# EEG_1.net
KiCad netlist of a schematic drawn in Altium Designer
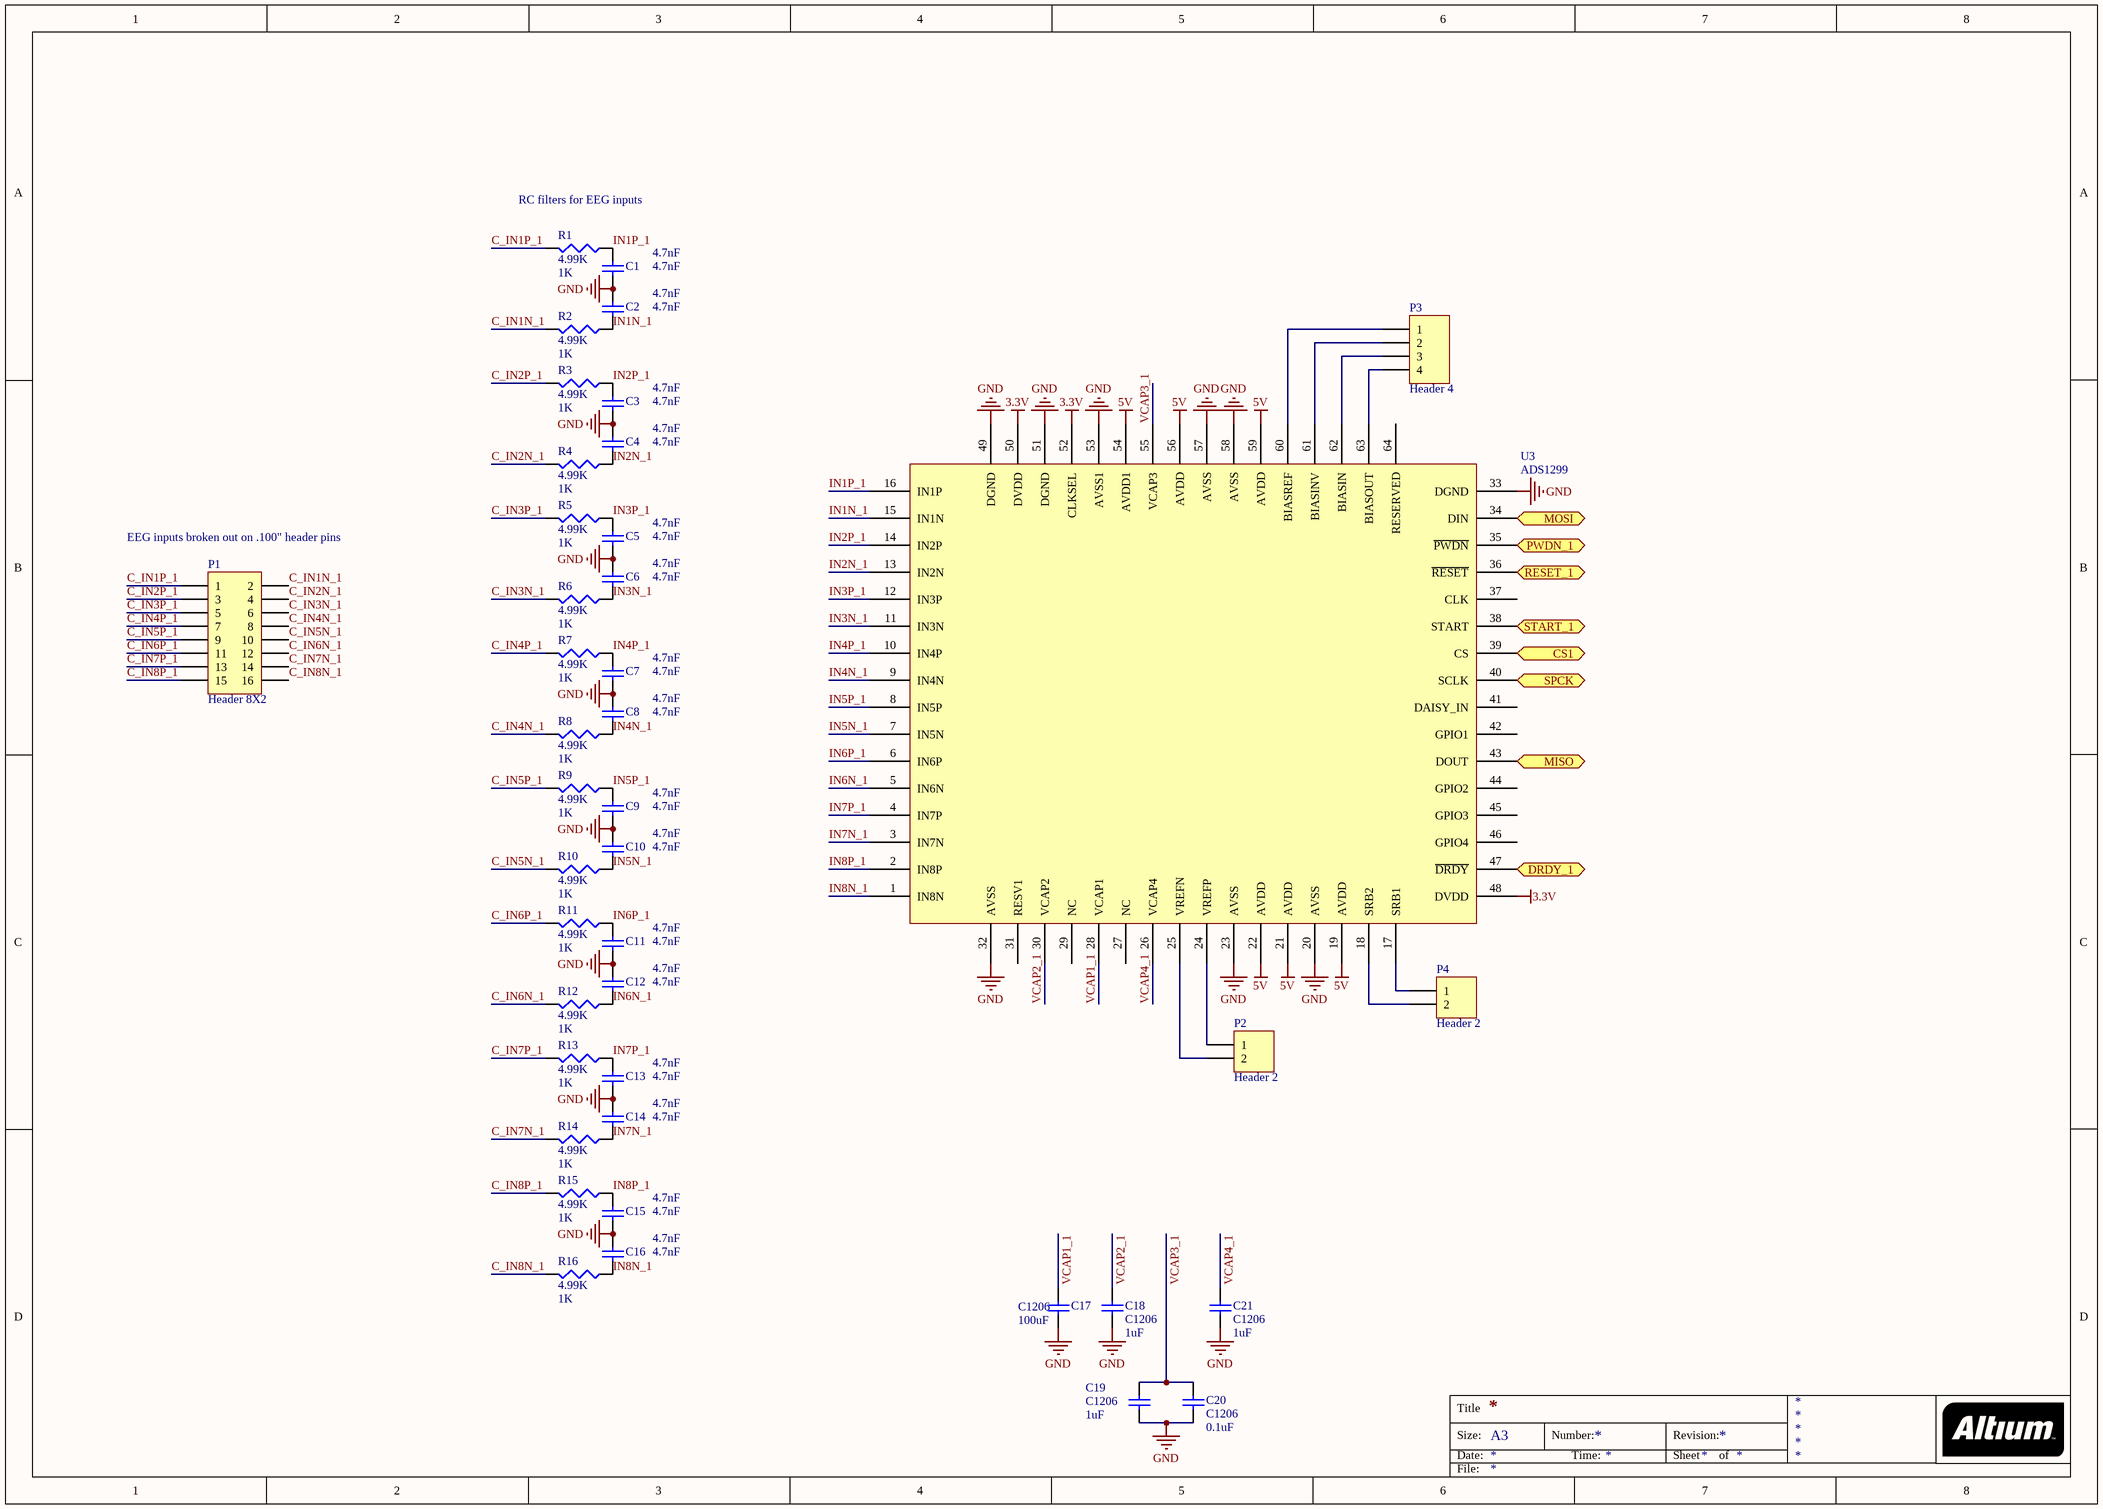
[diagram p0: EEG_1.SchDoc]

(export (version "E")
  (design (tool "Eeschema 10.0.6"))
  (components
    (comp (ref "C1")
      (value "4.7nF")
      (footprint "1608[0603]")
      (description "Capacitor (Semiconductor SIM Model)")
      (fields (field (name "ALTIUM_VALUE") "4.7nF") (field (name "PUBLISHER") "Altium Limited"))
      (libsource (lib "Miscellaneous Devices") (part "Cap Semi"))
    )
    (comp (ref "C2")
      (value "4.7nF")
      (footprint "1608[0603]")
      (description "Capacitor (Semiconductor SIM Model)")
      (fields (field (name "ALTIUM_VALUE") "4.7nF") (field (name "PUBLISHER") "Altium Limited"))
      (libsource (lib "Miscellaneous Devices") (part "Cap Semi"))
    )
    (comp (ref "C3")
      (value "4.7nF")
      (footprint "1608[0603]")
      (description "Capacitor (Semiconductor SIM Model)")
      (fields (field (name "ALTIUM_VALUE") "4.7nF") (field (name "PUBLISHER") "Altium Limited"))
      (libsource (lib "Miscellaneous Devices") (part "Cap Semi"))
    )
    (comp (ref "C4")
      (value "4.7nF")
      (footprint "1608[0603]")
      (description "Capacitor (Semiconductor SIM Model)")
      (fields (field (name "ALTIUM_VALUE") "4.7nF") (field (name "PUBLISHER") "Altium Limited"))
      (libsource (lib "Miscellaneous Devices") (part "Cap Semi"))
    )
    (comp (ref "C5")
      (value "4.7nF")
      (footprint "1608[0603]")
      (description "Capacitor (Semiconductor SIM Model)")
      (fields (field (name "ALTIUM_VALUE") "4.7nF") (field (name "PUBLISHER") "Altium Limited"))
      (libsource (lib "Miscellaneous Devices") (part "Cap Semi"))
    )
    (comp (ref "C6")
      (value "4.7nF")
      (footprint "1608[0603]")
      (description "Capacitor (Semiconductor SIM Model)")
      (fields (field (name "ALTIUM_VALUE") "4.7nF") (field (name "PUBLISHER") "Altium Limited"))
      (libsource (lib "Miscellaneous Devices") (part "Cap Semi"))
    )
    (comp (ref "C7")
      (value "4.7nF")
      (footprint "1608[0603]")
      (description "Capacitor (Semiconductor SIM Model)")
      (fields (field (name "ALTIUM_VALUE") "4.7nF") (field (name "PUBLISHER") "Altium Limited"))
      (libsource (lib "Miscellaneous Devices") (part "Cap Semi"))
    )
    (comp (ref "C8")
      (value "4.7nF")
      (footprint "1608[0603]")
      (description "Capacitor (Semiconductor SIM Model)")
      (fields (field (name "ALTIUM_VALUE") "4.7nF") (field (name "PUBLISHER") "Altium Limited"))
      (libsource (lib "Miscellaneous Devices") (part "Cap Semi"))
    )
    (comp (ref "C9")
      (value "4.7nF")
      (footprint "1608[0603]")
      (description "Capacitor (Semiconductor SIM Model)")
      (fields (field (name "ALTIUM_VALUE") "4.7nF") (field (name "PUBLISHER") "Altium Limited"))
      (libsource (lib "Miscellaneous Devices") (part "Cap Semi"))
    )
    (comp (ref "C10")
      (value "4.7nF")
      (footprint "1608[0603]")
      (description "Capacitor (Semiconductor SIM Model)")
      (fields (field (name "ALTIUM_VALUE") "4.7nF") (field (name "PUBLISHER") "Altium Limited"))
      (libsource (lib "Miscellaneous Devices") (part "Cap Semi"))
    )
    (comp (ref "C11")
      (value "4.7nF")
      (footprint "1608[0603]")
      (description "Capacitor (Semiconductor SIM Model)")
      (fields (field (name "ALTIUM_VALUE") "4.7nF") (field (name "PUBLISHER") "Altium Limited"))
      (libsource (lib "Miscellaneous Devices") (part "Cap Semi"))
    )
    (comp (ref "C12")
      (value "4.7nF")
      (footprint "1608[0603]")
      (description "Capacitor (Semiconductor SIM Model)")
      (fields (field (name "ALTIUM_VALUE") "4.7nF") (field (name "PUBLISHER") "Altium Limited"))
      (libsource (lib "Miscellaneous Devices") (part "Cap Semi"))
    )
    (comp (ref "C13")
      (value "4.7nF")
      (footprint "1608[0603]")
      (description "Capacitor (Semiconductor SIM Model)")
      (fields (field (name "ALTIUM_VALUE") "4.7nF") (field (name "PUBLISHER") "Altium Limited"))
      (libsource (lib "Miscellaneous Devices") (part "Cap Semi"))
    )
    (comp (ref "C14")
      (value "4.7nF")
      (footprint "1608[0603]")
      (description "Capacitor (Semiconductor SIM Model)")
      (fields (field (name "ALTIUM_VALUE") "4.7nF") (field (name "PUBLISHER") "Altium Limited"))
      (libsource (lib "Miscellaneous Devices") (part "Cap Semi"))
    )
    (comp (ref "C15")
      (value "4.7nF")
      (footprint "1608[0603]")
      (description "Capacitor (Semiconductor SIM Model)")
      (fields (field (name "ALTIUM_VALUE") "4.7nF") (field (name "PUBLISHER") "Altium Limited"))
      (libsource (lib "Miscellaneous Devices") (part "Cap Semi"))
    )
    (comp (ref "C16")
      (value "4.7nF")
      (footprint "1608[0603]")
      (description "Capacitor (Semiconductor SIM Model)")
      (fields (field (name "ALTIUM_VALUE") "4.7nF") (field (name "PUBLISHER") "Altium Limited"))
      (libsource (lib "Miscellaneous Devices") (part "Cap Semi"))
    )
    (comp (ref "C17")
      (value "C1206")
      (footprint "1608[0603]")
      (description "Capacitor (Semiconductor SIM Model)")
      (fields (field (name "ALTIUM_VALUE") "100uF") (field (name "PUBLISHER") "Altium Limited"))
      (libsource (lib "Miscellaneous Devices") (part "Cap Semi"))
    )
    (comp (ref "C18")
      (value "C1206")
      (footprint "1608[0603]")
      (description "Capacitor (Semiconductor SIM Model)")
      (fields (field (name "ALTIUM_VALUE") "1uF") (field (name "PUBLISHER") "Altium Limited"))
      (libsource (lib "Miscellaneous Devices") (part "Cap Semi"))
    )
    (comp (ref "C19")
      (value "C1206")
      (footprint "1608[0603]")
      (description "Capacitor (Semiconductor SIM Model)")
      (fields (field (name "ALTIUM_VALUE") "1uF") (field (name "PUBLISHER") "Altium Limited"))
      (libsource (lib "Miscellaneous Devices") (part "Cap Semi"))
    )
    (comp (ref "C20")
      (value "C1206")
      (footprint "1608[0603]")
      (description "Capacitor (Semiconductor SIM Model)")
      (fields (field (name "ALTIUM_VALUE") "0.1uF") (field (name "PUBLISHER") "Altium Limited"))
      (libsource (lib "Miscellaneous Devices") (part "Cap Semi"))
    )
    (comp (ref "C21")
      (value "C1206")
      (footprint "1608[0603]")
      (description "Capacitor (Semiconductor SIM Model)")
      (fields (field (name "ALTIUM_VALUE") "1uF") (field (name "PUBLISHER") "Altium Limited"))
      (libsource (lib "Miscellaneous Devices") (part "Cap Semi"))
    )
    (comp (ref "P1")
      (value "Header 8X2")
      (footprint "HDR2X8")
      (description "Header, 8-Pin, Dual row")
      (fields (field (name "PUBLISHER") "Altium Limited"))
      (libsource (lib "Miscellaneous Connectors") (part "Header 8X2"))
    )
    (comp (ref "P2")
      (value "Header 2")
      (footprint "HDR1X2")
      (description "Header, 2-Pin")
      (fields (field (name "PUBLISHER") "Altium Limited"))
      (libsource (lib "Miscellaneous Connectors") (part "Header 2"))
    )
    (comp (ref "P3")
      (value "Header 4")
      (footprint "HDR1X4")
      (description "Header, 4-Pin")
      (fields (field (name "PUBLISHER") "Altium Limited"))
      (libsource (lib "Miscellaneous Connectors") (part "Header 4"))
    )
    (comp (ref "P4")
      (value "Header 2")
      (footprint "HDR1X2")
      (description "Header, 2-Pin")
      (fields (field (name "PUBLISHER") "Altium Limited"))
      (libsource (lib "Miscellaneous Connectors") (part "Header 2"))
    )
    (comp (ref "R1")
      (value "4.99K")
      (footprint "1608[0603]")
      (description "Resistor")
      (fields (field (name "ALTIUM_VALUE") "1K") (field (name "PUBLISHER") "Altium Limited"))
      (libsource (lib "Miscellaneous Devices") (part "Res3"))
    )
    (comp (ref "R2")
      (value "4.99K")
      (footprint "1608[0603]")
      (description "Resistor")
      (fields (field (name "ALTIUM_VALUE") "1K") (field (name "PUBLISHER") "Altium Limited"))
      (libsource (lib "Miscellaneous Devices") (part "Res3"))
    )
    (comp (ref "R3")
      (value "4.99K")
      (footprint "1608[0603]")
      (description "Resistor")
      (fields (field (name "ALTIUM_VALUE") "1K") (field (name "PUBLISHER") "Altium Limited"))
      (libsource (lib "Miscellaneous Devices") (part "Res3"))
    )
    (comp (ref "R4")
      (value "4.99K")
      (footprint "1608[0603]")
      (description "Resistor")
      (fields (field (name "ALTIUM_VALUE") "1K") (field (name "PUBLISHER") "Altium Limited"))
      (libsource (lib "Miscellaneous Devices") (part "Res3"))
    )
    (comp (ref "R5")
      (value "4.99K")
      (footprint "1608[0603]")
      (description "Resistor")
      (fields (field (name "ALTIUM_VALUE") "1K") (field (name "PUBLISHER") "Altium Limited"))
      (libsource (lib "Miscellaneous Devices") (part "Res3"))
    )
    (comp (ref "R6")
      (value "4.99K")
      (footprint "1608[0603]")
      (description "Resistor")
      (fields (field (name "ALTIUM_VALUE") "1K") (field (name "PUBLISHER") "Altium Limited"))
      (libsource (lib "Miscellaneous Devices") (part "Res3"))
    )
    (comp (ref "R7")
      (value "4.99K")
      (footprint "1608[0603]")
      (description "Resistor")
      (fields (field (name "ALTIUM_VALUE") "1K") (field (name "PUBLISHER") "Altium Limited"))
      (libsource (lib "Miscellaneous Devices") (part "Res3"))
    )
    (comp (ref "R8")
      (value "4.99K")
      (footprint "1608[0603]")
      (description "Resistor")
      (fields (field (name "ALTIUM_VALUE") "1K") (field (name "PUBLISHER") "Altium Limited"))
      (libsource (lib "Miscellaneous Devices") (part "Res3"))
    )
    (comp (ref "R9")
      (value "4.99K")
      (footprint "1608[0603]")
      (description "Resistor")
      (fields (field (name "ALTIUM_VALUE") "1K") (field (name "PUBLISHER") "Altium Limited"))
      (libsource (lib "Miscellaneous Devices") (part "Res3"))
    )
    (comp (ref "R10")
      (value "4.99K")
      (footprint "1608[0603]")
      (description "Resistor")
      (fields (field (name "ALTIUM_VALUE") "1K") (field (name "PUBLISHER") "Altium Limited"))
      (libsource (lib "Miscellaneous Devices") (part "Res3"))
    )
    (comp (ref "R11")
      (value "4.99K")
      (footprint "1608[0603]")
      (description "Resistor")
      (fields (field (name "ALTIUM_VALUE") "1K") (field (name "PUBLISHER") "Altium Limited"))
      (libsource (lib "Miscellaneous Devices") (part "Res3"))
    )
    (comp (ref "R12")
      (value "4.99K")
      (footprint "1608[0603]")
      (description "Resistor")
      (fields (field (name "ALTIUM_VALUE") "1K") (field (name "PUBLISHER") "Altium Limited"))
      (libsource (lib "Miscellaneous Devices") (part "Res3"))
    )
    (comp (ref "R13")
      (value "4.99K")
      (footprint "1608[0603]")
      (description "Resistor")
      (fields (field (name "ALTIUM_VALUE") "1K") (field (name "PUBLISHER") "Altium Limited"))
      (libsource (lib "Miscellaneous Devices") (part "Res3"))
    )
    (comp (ref "R14")
      (value "4.99K")
      (footprint "1608[0603]")
      (description "Resistor")
      (fields (field (name "ALTIUM_VALUE") "1K") (field (name "PUBLISHER") "Altium Limited"))
      (libsource (lib "Miscellaneous Devices") (part "Res3"))
    )
    (comp (ref "R15")
      (value "4.99K")
      (footprint "1608[0603]")
      (description "Resistor")
      (fields (field (name "ALTIUM_VALUE") "1K") (field (name "PUBLISHER") "Altium Limited"))
      (libsource (lib "Miscellaneous Devices") (part "Res3"))
    )
    (comp (ref "R16")
      (value "4.99K")
      (footprint "1608[0603]")
      (description "Resistor")
      (fields (field (name "ALTIUM_VALUE") "1K") (field (name "PUBLISHER") "Altium Limited"))
      (libsource (lib "Miscellaneous Devices") (part "Res3"))
    )
    (comp (ref "U3")
      (value "ADS1299")
      (footprint "ADS1299 Plastic QFP")
      (libsource (lib "ADS1299") (part "ADS1299"))
    )
  )
  (nets
    (net (code "1") (name "/CS1") (class "Default")
      (node (ref "U3") (pin "39") (pinfunction "CS_39") (pintype "passive"))
    )
    (net (code "2") (name "/C_IN1N_1") (class "Default")
      (node (ref "P1") (pin "2") (pinfunction "2_2") (pintype "passive"))
      (node (ref "R2") (pin "2") (pinfunction "2_2") (pintype "passive"))
    )
    (net (code "3") (name "/C_IN1P_1") (class "Default")
      (node (ref "P1") (pin "1") (pinfunction "1_1") (pintype "passive"))
      (node (ref "R1") (pin "2") (pinfunction "2_2") (pintype "passive"))
    )
    (net (code "4") (name "/C_IN2N_1") (class "Default")
      (node (ref "P1") (pin "4") (pinfunction "4_4") (pintype "passive"))
      (node (ref "R4") (pin "2") (pinfunction "2_2") (pintype "passive"))
    )
    (net (code "5") (name "/C_IN2P_1") (class "Default")
      (node (ref "P1") (pin "3") (pinfunction "3_3") (pintype "passive"))
      (node (ref "R3") (pin "2") (pinfunction "2_2") (pintype "passive"))
    )
    (net (code "6") (name "/C_IN3N_1") (class "Default")
      (node (ref "P1") (pin "6") (pinfunction "6_6") (pintype "passive"))
      (node (ref "R6") (pin "2") (pinfunction "2_2") (pintype "passive"))
    )
    (net (code "7") (name "/C_IN3P_1") (class "Default")
      (node (ref "P1") (pin "5") (pinfunction "5_5") (pintype "passive"))
      (node (ref "R5") (pin "2") (pinfunction "2_2") (pintype "passive"))
    )
    (net (code "8") (name "/C_IN4N_1") (class "Default")
      (node (ref "P1") (pin "8") (pinfunction "8_8") (pintype "passive"))
      (node (ref "R8") (pin "2") (pinfunction "2_2") (pintype "passive"))
    )
    (net (code "9") (name "/C_IN4P_1") (class "Default")
      (node (ref "P1") (pin "7") (pinfunction "7_7") (pintype "passive"))
      (node (ref "R7") (pin "2") (pinfunction "2_2") (pintype "passive"))
    )
    (net (code "10") (name "/C_IN5N_1") (class "Default")
      (node (ref "P1") (pin "10") (pinfunction "10_10") (pintype "passive"))
      (node (ref "R10") (pin "2") (pinfunction "2_2") (pintype "passive"))
    )
    (net (code "11") (name "/C_IN5P_1") (class "Default")
      (node (ref "P1") (pin "9") (pinfunction "9_9") (pintype "passive"))
      (node (ref "R9") (pin "2") (pinfunction "2_2") (pintype "passive"))
    )
    (net (code "12") (name "/C_IN6N_1") (class "Default")
      (node (ref "P1") (pin "12") (pinfunction "12_12") (pintype "passive"))
      (node (ref "R12") (pin "2") (pinfunction "2_2") (pintype "passive"))
    )
    (net (code "13") (name "/C_IN6P_1") (class "Default")
      (node (ref "P1") (pin "11") (pinfunction "11_11") (pintype "passive"))
      (node (ref "R11") (pin "2") (pinfunction "2_2") (pintype "passive"))
    )
    (net (code "14") (name "/C_IN7N_1") (class "Default")
      (node (ref "P1") (pin "14") (pinfunction "14_14") (pintype "passive"))
      (node (ref "R14") (pin "2") (pinfunction "2_2") (pintype "passive"))
    )
    (net (code "15") (name "/C_IN7P_1") (class "Default")
      (node (ref "P1") (pin "13") (pinfunction "13_13") (pintype "passive"))
      (node (ref "R13") (pin "2") (pinfunction "2_2") (pintype "passive"))
    )
    (net (code "16") (name "/C_IN8N_1") (class "Default")
      (node (ref "P1") (pin "16") (pinfunction "16_16") (pintype "passive"))
      (node (ref "R16") (pin "2") (pinfunction "2_2") (pintype "passive"))
    )
    (net (code "17") (name "/C_IN8P_1") (class "Default")
      (node (ref "P1") (pin "15") (pinfunction "15_15") (pintype "passive"))
      (node (ref "R15") (pin "2") (pinfunction "2_2") (pintype "passive"))
    )
    (net (code "18") (name "/DRDY_1") (class "Default")
      (node (ref "U3") (pin "47") (pinfunction "~{DRDY}_47") (pintype "passive"))
    )
    (net (code "19") (name "/IN1N_1") (class "Default")
      (node (ref "C2") (pin "1") (pinfunction "1_1") (pintype "passive"))
      (node (ref "R2") (pin "1") (pinfunction "1_1") (pintype "passive"))
      (node (ref "U3") (pin "15") (pinfunction "IN1N_15") (pintype "passive"))
    )
    (net (code "20") (name "/IN1P_1") (class "Default")
      (node (ref "C1") (pin "2") (pinfunction "2_2") (pintype "passive"))
      (node (ref "R1") (pin "1") (pinfunction "1_1") (pintype "passive"))
      (node (ref "U3") (pin "16") (pinfunction "IN1P_16") (pintype "passive"))
    )
    (net (code "21") (name "/IN2N_1") (class "Default")
      (node (ref "C4") (pin "1") (pinfunction "1_1") (pintype "passive"))
      (node (ref "R4") (pin "1") (pinfunction "1_1") (pintype "passive"))
      (node (ref "U3") (pin "13") (pinfunction "IN2N_13") (pintype "passive"))
    )
    (net (code "22") (name "/IN2P_1") (class "Default")
      (node (ref "C3") (pin "2") (pinfunction "2_2") (pintype "passive"))
      (node (ref "R3") (pin "1") (pinfunction "1_1") (pintype "passive"))
      (node (ref "U3") (pin "14") (pinfunction "IN2P_14") (pintype "passive"))
    )
    (net (code "23") (name "/IN3N_1") (class "Default")
      (node (ref "C6") (pin "1") (pinfunction "1_1") (pintype "passive"))
      (node (ref "R6") (pin "1") (pinfunction "1_1") (pintype "passive"))
      (node (ref "U3") (pin "11") (pinfunction "IN3N_11") (pintype "passive"))
    )
    (net (code "24") (name "/IN3P_1") (class "Default")
      (node (ref "C5") (pin "2") (pinfunction "2_2") (pintype "passive"))
      (node (ref "R5") (pin "1") (pinfunction "1_1") (pintype "passive"))
      (node (ref "U3") (pin "12") (pinfunction "IN3P_12") (pintype "passive"))
    )
    (net (code "25") (name "/IN4N_1") (class "Default")
      (node (ref "C8") (pin "1") (pinfunction "1_1") (pintype "passive"))
      (node (ref "R8") (pin "1") (pinfunction "1_1") (pintype "passive"))
      (node (ref "U3") (pin "9") (pinfunction "IN4N_9") (pintype "passive"))
    )
    (net (code "26") (name "/IN4P_1") (class "Default")
      (node (ref "C7") (pin "2") (pinfunction "2_2") (pintype "passive"))
      (node (ref "R7") (pin "1") (pinfunction "1_1") (pintype "passive"))
      (node (ref "U3") (pin "10") (pinfunction "IN4P_10") (pintype "passive"))
    )
    (net (code "27") (name "/IN5N_1") (class "Default")
      (node (ref "C10") (pin "1") (pinfunction "1_1") (pintype "passive"))
      (node (ref "R10") (pin "1") (pinfunction "1_1") (pintype "passive"))
      (node (ref "U3") (pin "7") (pinfunction "IN5N_7") (pintype "passive"))
    )
    (net (code "28") (name "/IN5P_1") (class "Default")
      (node (ref "C9") (pin "2") (pinfunction "2_2") (pintype "passive"))
      (node (ref "R9") (pin "1") (pinfunction "1_1") (pintype "passive"))
      (node (ref "U3") (pin "8") (pinfunction "IN5P_8") (pintype "passive"))
    )
    (net (code "29") (name "/IN6N_1") (class "Default")
      (node (ref "C12") (pin "1") (pinfunction "1_1") (pintype "passive"))
      (node (ref "R12") (pin "1") (pinfunction "1_1") (pintype "passive"))
      (node (ref "U3") (pin "5") (pinfunction "IN6N_5") (pintype "passive"))
    )
    (net (code "30") (name "/IN6P_1") (class "Default")
      (node (ref "C11") (pin "2") (pinfunction "2_2") (pintype "passive"))
      (node (ref "R11") (pin "1") (pinfunction "1_1") (pintype "passive"))
      (node (ref "U3") (pin "6") (pinfunction "IN6P_6") (pintype "passive"))
    )
    (net (code "31") (name "/IN7N_1") (class "Default")
      (node (ref "C14") (pin "1") (pinfunction "1_1") (pintype "passive"))
      (node (ref "R14") (pin "1") (pinfunction "1_1") (pintype "passive"))
      (node (ref "U3") (pin "3") (pinfunction "IN7N_3") (pintype "passive"))
    )
    (net (code "32") (name "/IN7P_1") (class "Default")
      (node (ref "C13") (pin "2") (pinfunction "2_2") (pintype "passive"))
      (node (ref "R13") (pin "1") (pinfunction "1_1") (pintype "passive"))
      (node (ref "U3") (pin "4") (pinfunction "IN7P_4") (pintype "passive"))
    )
    (net (code "33") (name "/IN8N_1") (class "Default")
      (node (ref "C16") (pin "1") (pinfunction "1_1") (pintype "passive"))
      (node (ref "R16") (pin "1") (pinfunction "1_1") (pintype "passive"))
      (node (ref "U3") (pin "1") (pinfunction "IN8N_1") (pintype "passive"))
    )
    (net (code "34") (name "/IN8P_1") (class "Default")
      (node (ref "C15") (pin "2") (pinfunction "2_2") (pintype "passive"))
      (node (ref "R15") (pin "1") (pinfunction "1_1") (pintype "passive"))
      (node (ref "U3") (pin "2") (pinfunction "IN8P_2") (pintype "passive"))
    )
    (net (code "35") (name "/MISO") (class "Default")
      (node (ref "U3") (pin "43") (pinfunction "DOUT_43") (pintype "passive"))
    )
    (net (code "36") (name "/MOSI") (class "Default")
      (node (ref "U3") (pin "34") (pinfunction "DIN_34") (pintype "passive"))
    )
    (net (code "37") (name "/PWDN_1") (class "Default")
      (node (ref "U3") (pin "35") (pinfunction "~{PWDN}_35") (pintype "passive"))
    )
    (net (code "38") (name "/RESET_1") (class "Default")
      (node (ref "U3") (pin "36") (pinfunction "~{RESET}_36") (pintype "passive"))
    )
    (net (code "39") (name "/SPCK") (class "Default")
      (node (ref "U3") (pin "40") (pinfunction "SCLK_40") (pintype "passive"))
    )
    (net (code "40") (name "/START_1") (class "Default")
      (node (ref "U3") (pin "38") (pinfunction "START_38") (pintype "passive"))
    )
    (net (code "41") (name "/VCAP1_1") (class "Default")
      (node (ref "C17") (pin "1") (pinfunction "1_1") (pintype "passive"))
      (node (ref "U3") (pin "28") (pinfunction "VCAP1_28") (pintype "passive"))
    )
    (net (code "42") (name "/VCAP2_1") (class "Default")
      (node (ref "C18") (pin "2") (pinfunction "2_2") (pintype "passive"))
      (node (ref "U3") (pin "30") (pinfunction "VCAP2_30") (pintype "passive"))
    )
    (net (code "43") (name "/VCAP3_1") (class "Default")
      (node (ref "C19") (pin "1") (pinfunction "1_1") (pintype "passive"))
      (node (ref "C20") (pin "2") (pinfunction "2_2") (pintype "passive"))
      (node (ref "U3") (pin "55") (pinfunction "VCAP3_55") (pintype "passive"))
    )
    (net (code "44") (name "/VCAP4_1") (class "Default")
      (node (ref "C21") (pin "2") (pinfunction "2_2") (pintype "passive"))
      (node (ref "U3") (pin "26") (pinfunction "VCAP4_26") (pintype "passive"))
    )
    (net (code "45") (name "3.3V") (class "Default")
      (node (ref "U3") (pin "48") (pinfunction "DVDD_48") (pintype "passive"))
      (node (ref "U3") (pin "50") (pinfunction "DVDD_50") (pintype "passive"))
      (node (ref "U3") (pin "52") (pinfunction "CLKSEL_52") (pintype "passive"))
    )
    (net (code "46") (name "5V") (class "Default")
      (node (ref "U3") (pin "19") (pinfunction "AVDD_19") (pintype "passive"))
      (node (ref "U3") (pin "21") (pinfunction "AVDD_21") (pintype "passive"))
      (node (ref "U3") (pin "22") (pinfunction "AVDD_22") (pintype "passive"))
      (node (ref "U3") (pin "54") (pinfunction "AVDD1_54") (pintype "passive"))
      (node (ref "U3") (pin "56") (pinfunction "AVDD_56") (pintype "passive"))
      (node (ref "U3") (pin "59") (pinfunction "AVDD_59") (pintype "passive"))
    )
    (net (code "47") (name "GND") (class "Default")
      (node (ref "C1") (pin "1") (pinfunction "1_1") (pintype "passive"))
      (node (ref "C10") (pin "2") (pinfunction "2_2") (pintype "passive"))
      (node (ref "C11") (pin "1") (pinfunction "1_1") (pintype "passive"))
      (node (ref "C12") (pin "2") (pinfunction "2_2") (pintype "passive"))
      (node (ref "C13") (pin "1") (pinfunction "1_1") (pintype "passive"))
      (node (ref "C14") (pin "2") (pinfunction "2_2") (pintype "passive"))
      (node (ref "C15") (pin "1") (pinfunction "1_1") (pintype "passive"))
      (node (ref "C16") (pin "2") (pinfunction "2_2") (pintype "passive"))
      (node (ref "C17") (pin "2") (pinfunction "2_2") (pintype "passive"))
      (node (ref "C18") (pin "1") (pinfunction "1_1") (pintype "passive"))
      (node (ref "C19") (pin "2") (pinfunction "2_2") (pintype "passive"))
      (node (ref "C2") (pin "2") (pinfunction "2_2") (pintype "passive"))
      (node (ref "C20") (pin "1") (pinfunction "1_1") (pintype "passive"))
      (node (ref "C21") (pin "1") (pinfunction "1_1") (pintype "passive"))
      (node (ref "C3") (pin "1") (pinfunction "1_1") (pintype "passive"))
      (node (ref "C4") (pin "2") (pinfunction "2_2") (pintype "passive"))
      (node (ref "C5") (pin "1") (pinfunction "1_1") (pintype "passive"))
      (node (ref "C6") (pin "2") (pinfunction "2_2") (pintype "passive"))
      (node (ref "C7") (pin "1") (pinfunction "1_1") (pintype "passive"))
      (node (ref "C8") (pin "2") (pinfunction "2_2") (pintype "passive"))
      (node (ref "C9") (pin "1") (pinfunction "1_1") (pintype "passive"))
      (node (ref "U3") (pin "20") (pinfunction "AVSS_20") (pintype "passive"))
      (node (ref "U3") (pin "23") (pinfunction "AVSS_23") (pintype "passive"))
      (node (ref "U3") (pin "32") (pinfunction "AVSS_32") (pintype "passive"))
      (node (ref "U3") (pin "33") (pinfunction "DGND_33") (pintype "passive"))
      (node (ref "U3") (pin "49") (pinfunction "DGND_49") (pintype "passive"))
      (node (ref "U3") (pin "51") (pinfunction "DGND_51") (pintype "passive"))
      (node (ref "U3") (pin "53") (pinfunction "AVSS1_53") (pintype "passive"))
      (node (ref "U3") (pin "57") (pinfunction "AVSS_57") (pintype "passive"))
      (node (ref "U3") (pin "58") (pinfunction "AVSS_58") (pintype "passive"))
    )
    (net (code "48") (name "Net-(U3-BIASIN)") (class "Default")
      (node (ref "P3") (pin "3") (pinfunction "3_3") (pintype "passive"))
      (node (ref "U3") (pin "62") (pinfunction "BIASIN_62") (pintype "passive"))
    )
    (net (code "49") (name "Net-(U3-BIASINV)") (class "Default")
      (node (ref "P3") (pin "2") (pinfunction "2_2") (pintype "passive"))
      (node (ref "U3") (pin "61") (pinfunction "BIASINV_61") (pintype "passive"))
    )
    (net (code "50") (name "Net-(U3-BIASOUT)") (class "Default")
      (node (ref "P3") (pin "4") (pinfunction "4_4") (pintype "passive"))
      (node (ref "U3") (pin "63") (pinfunction "BIASOUT_63") (pintype "passive"))
    )
    (net (code "51") (name "Net-(U3-BIASREF)") (class "Default")
      (node (ref "P3") (pin "1") (pinfunction "1_1") (pintype "passive"))
      (node (ref "U3") (pin "60") (pinfunction "BIASREF_60") (pintype "passive"))
    )
    (net (code "52") (name "Net-(U3-SRB1)") (class "Default")
      (node (ref "P4") (pin "1") (pinfunction "1_1") (pintype "passive"))
      (node (ref "U3") (pin "17") (pinfunction "SRB1_17") (pintype "passive"))
    )
    (net (code "53") (name "Net-(U3-SRB2)") (class "Default")
      (node (ref "P4") (pin "2") (pinfunction "2_2") (pintype "passive"))
      (node (ref "U3") (pin "18") (pinfunction "SRB2_18") (pintype "passive"))
    )
    (net (code "54") (name "Net-(U3-VREFN)") (class "Default")
      (node (ref "P2") (pin "2") (pinfunction "2_2") (pintype "passive"))
      (node (ref "U3") (pin "25") (pinfunction "VREFN_25") (pintype "passive"))
    )
    (net (code "55") (name "Net-(U3-VREFP)") (class "Default")
      (node (ref "P2") (pin "1") (pinfunction "1_1") (pintype "passive"))
      (node (ref "U3") (pin "24") (pinfunction "VREFP_24") (pintype "passive"))
    )
    (net (code "56") (name "unconnected-(U3-CLK-Pad37)") (class "Default")
      (node (ref "U3") (pin "37") (pinfunction "CLK_37") (pintype "passive"))
    )
    (net (code "57") (name "unconnected-(U3-DAISY_IN-Pad41)") (class "Default")
      (node (ref "U3") (pin "41") (pinfunction "DAISY_IN_41") (pintype "passive"))
    )
    (net (code "58") (name "unconnected-(U3-GPIO1-Pad42)") (class "Default")
      (node (ref "U3") (pin "42") (pinfunction "GPIO1_42") (pintype "passive"))
    )
    (net (code "59") (name "unconnected-(U3-GPIO2-Pad44)") (class "Default")
      (node (ref "U3") (pin "44") (pinfunction "GPIO2_44") (pintype "passive"))
    )
    (net (code "60") (name "unconnected-(U3-GPIO3-Pad45)") (class "Default")
      (node (ref "U3") (pin "45") (pinfunction "GPIO3_45") (pintype "passive"))
    )
    (net (code "61") (name "unconnected-(U3-GPIO4-Pad46)") (class "Default")
      (node (ref "U3") (pin "46") (pinfunction "GPIO4_46") (pintype "passive"))
    )
    (net (code "62") (name "unconnected-(U3-NC-Pad27)") (class "Default")
      (node (ref "U3") (pin "27") (pinfunction "NC_27") (pintype "passive"))
    )
    (net (code "63") (name "unconnected-(U3-NC-Pad29)") (class "Default")
      (node (ref "U3") (pin "29") (pinfunction "NC_29") (pintype "passive"))
    )
    (net (code "64") (name "unconnected-(U3-RESERVED-Pad64)") (class "Default")
      (node (ref "U3") (pin "64") (pinfunction "RESERVED_64") (pintype "passive"))
    )
    (net (code "65") (name "unconnected-(U3-RESV1-Pad31)") (class "Default")
      (node (ref "U3") (pin "31") (pinfunction "RESV1_31") (pintype "passive"))
    )
  )
)
